# CON_MC_XMC_J11_64PIN.net
KiCad netlist of a schematic drawn in Altium Designer
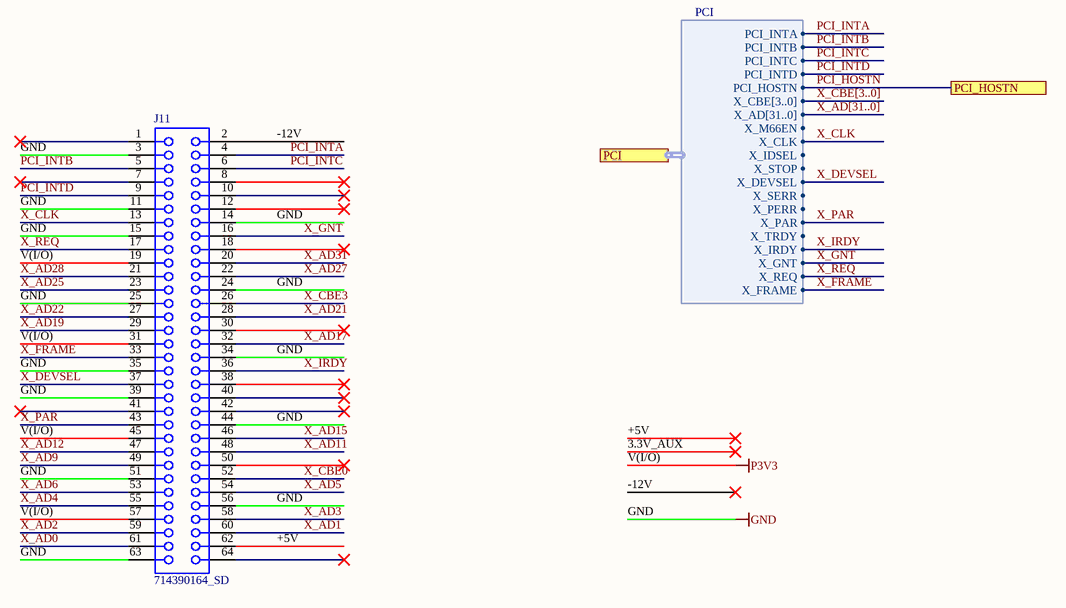
[diagram p0: CON_MC_XMC_J11_64PIN.SchDoc]

(export (version "E")
  (design (tool "Eeschema 10.0.6"))
  (components
    (comp (ref "J11")
      (value "714390164_SD")
      (footprint "BTB1-2V64F")
      (description "Board-to-Board Connector, Vertical, 2-Row, Pitch 1mm, 64-Position, Female")
      (fields (field (name "PUBLISHER") "Altium"))
      (libsource (lib "Altium Shanghai") (part "CMP-0001-00081-1"))
    )
  )
  (nets
    (net (code "15") (name "/+5V") (class "Default")
      (node (ref "J11") (pin "62") (pinfunction "62_62") (pintype "passive+no_connect"))
    )
    (net (code "16") (name "/-12V") (class "Default")
      (node (ref "J11") (pin "2") (pinfunction "2_2") (pintype "passive+no_connect"))
    )
    (net (code "19") (name "/PCI_INTA") (class "Default")
      (node (ref "J11") (pin "4") (pinfunction "4_4") (pintype "passive"))
    )
    (net (code "20") (name "/PCI_INTB") (class "Default")
      (node (ref "J11") (pin "5") (pinfunction "5_5") (pintype "passive"))
    )
    (net (code "21") (name "/PCI_INTC") (class "Default")
      (node (ref "J11") (pin "6") (pinfunction "6_6") (pintype "passive"))
    )
    (net (code "22") (name "/PCI_INTD") (class "Default")
      (node (ref "J11") (pin "9") (pinfunction "9_9") (pintype "passive"))
    )
    (net (code "24") (name "/X_AD0") (class "Default")
      (node (ref "J11") (pin "61") (pinfunction "61_61") (pintype "passive"))
    )
    (net (code "25") (name "/X_AD1") (class "Default")
      (node (ref "J11") (pin "60") (pinfunction "60_60") (pintype "passive"))
    )
    (net (code "26") (name "/X_AD2") (class "Default")
      (node (ref "J11") (pin "59") (pinfunction "59_59") (pintype "passive"))
    )
    (net (code "27") (name "/X_AD3") (class "Default")
      (node (ref "J11") (pin "58") (pinfunction "58_58") (pintype "passive"))
    )
    (net (code "28") (name "/X_AD4") (class "Default")
      (node (ref "J11") (pin "55") (pinfunction "55_55") (pintype "passive"))
    )
    (net (code "29") (name "/X_AD5") (class "Default")
      (node (ref "J11") (pin "54") (pinfunction "54_54") (pintype "passive"))
    )
    (net (code "30") (name "/X_AD6") (class "Default")
      (node (ref "J11") (pin "53") (pinfunction "53_53") (pintype "passive"))
    )
    (net (code "31") (name "/X_AD9") (class "Default")
      (node (ref "J11") (pin "49") (pinfunction "49_49") (pintype "passive"))
    )
    (net (code "32") (name "/X_AD11") (class "Default")
      (node (ref "J11") (pin "48") (pinfunction "48_48") (pintype "passive"))
    )
    (net (code "33") (name "/X_AD12") (class "Default")
      (node (ref "J11") (pin "47") (pinfunction "47_47") (pintype "passive"))
    )
    (net (code "34") (name "/X_AD15") (class "Default")
      (node (ref "J11") (pin "46") (pinfunction "46_46") (pintype "passive"))
    )
    (net (code "35") (name "/X_AD17") (class "Default")
      (node (ref "J11") (pin "32") (pinfunction "32_32") (pintype "passive"))
    )
    (net (code "36") (name "/X_AD19") (class "Default")
      (node (ref "J11") (pin "29") (pinfunction "29_29") (pintype "passive"))
    )
    (net (code "37") (name "/X_AD21") (class "Default")
      (node (ref "J11") (pin "28") (pinfunction "28_28") (pintype "passive"))
    )
    (net (code "38") (name "/X_AD22") (class "Default")
      (node (ref "J11") (pin "27") (pinfunction "27_27") (pintype "passive"))
    )
    (net (code "39") (name "/X_AD25") (class "Default")
      (node (ref "J11") (pin "23") (pinfunction "23_23") (pintype "passive"))
    )
    (net (code "40") (name "/X_AD27") (class "Default")
      (node (ref "J11") (pin "22") (pinfunction "22_22") (pintype "passive"))
    )
    (net (code "41") (name "/X_AD28") (class "Default")
      (node (ref "J11") (pin "21") (pinfunction "21_21") (pintype "passive"))
    )
    (net (code "42") (name "/X_AD31") (class "Default")
      (node (ref "J11") (pin "20") (pinfunction "20_20") (pintype "passive"))
    )
    (net (code "44") (name "/X_CBE0") (class "Default")
      (node (ref "J11") (pin "52") (pinfunction "52_52") (pintype "passive"))
    )
    (net (code "45") (name "/X_CBE3") (class "Default")
      (node (ref "J11") (pin "26") (pinfunction "26_26") (pintype "passive"))
    )
    (net (code "46") (name "/X_CLK") (class "Default")
      (node (ref "J11") (pin "13") (pinfunction "13_13") (pintype "passive"))
    )
    (net (code "47") (name "/X_DEVSEL") (class "Default")
      (node (ref "J11") (pin "37") (pinfunction "37_37") (pintype "passive"))
    )
    (net (code "48") (name "/X_FRAME") (class "Default")
      (node (ref "J11") (pin "33") (pinfunction "33_33") (pintype "passive"))
    )
    (net (code "49") (name "/X_GNT") (class "Default")
      (node (ref "J11") (pin "16") (pinfunction "16_16") (pintype "passive"))
    )
    (net (code "50") (name "/X_IRDY") (class "Default")
      (node (ref "J11") (pin "36") (pinfunction "36_36") (pintype "passive"))
    )
    (net (code "51") (name "/X_PAR") (class "Default")
      (node (ref "J11") (pin "43") (pinfunction "43_43") (pintype "passive"))
    )
    (net (code "52") (name "/X_REQ") (class "Default")
      (node (ref "J11") (pin "17") (pinfunction "17_17") (pintype "passive"))
    )
    (net (code "54") (name "GND") (class "Default")
      (node (ref "J11") (pin "11") (pinfunction "11_11") (pintype "passive"))
      (node (ref "J11") (pin "14") (pinfunction "14_14") (pintype "passive"))
      (node (ref "J11") (pin "15") (pinfunction "15_15") (pintype "passive"))
      (node (ref "J11") (pin "24") (pinfunction "24_24") (pintype "passive"))
      (node (ref "J11") (pin "25") (pinfunction "25_25") (pintype "passive"))
      (node (ref "J11") (pin "3") (pinfunction "3_3") (pintype "passive"))
      (node (ref "J11") (pin "34") (pinfunction "34_34") (pintype "passive"))
      (node (ref "J11") (pin "35") (pinfunction "35_35") (pintype "passive"))
      (node (ref "J11") (pin "39") (pinfunction "39_39") (pintype "passive"))
      (node (ref "J11") (pin "44") (pinfunction "44_44") (pintype "passive"))
      (node (ref "J11") (pin "51") (pinfunction "51_51") (pintype "passive"))
      (node (ref "J11") (pin "56") (pinfunction "56_56") (pintype "passive"))
      (node (ref "J11") (pin "63") (pinfunction "63_63") (pintype "passive"))
    )
    (net (code "55") (name "P3V3") (class "Default")
      (node (ref "J11") (pin "19") (pinfunction "19_19") (pintype "passive"))
      (node (ref "J11") (pin "31") (pinfunction "31_31") (pintype "passive"))
      (node (ref "J11") (pin "45") (pinfunction "45_45") (pintype "passive"))
      (node (ref "J11") (pin "57") (pinfunction "57_57") (pintype "passive"))
    )
    (net (code "56") (name "unconnected-(J11-Pad1)") (class "Default")
      (node (ref "J11") (pin "1") (pinfunction "1_1") (pintype "passive+no_connect"))
    )
    (net (code "57") (name "unconnected-(J11-Pad7)") (class "Default")
      (node (ref "J11") (pin "7") (pinfunction "7_7") (pintype "passive+no_connect"))
    )
    (net (code "58") (name "unconnected-(J11-Pad8)") (class "Default")
      (node (ref "J11") (pin "8") (pinfunction "8_8") (pintype "passive+no_connect"))
    )
    (net (code "59") (name "unconnected-(J11-Pad10)") (class "Default")
      (node (ref "J11") (pin "10") (pinfunction "10_10") (pintype "passive+no_connect"))
    )
    (net (code "60") (name "unconnected-(J11-Pad12)") (class "Default")
      (node (ref "J11") (pin "12") (pinfunction "12_12") (pintype "passive+no_connect"))
    )
    (net (code "61") (name "unconnected-(J11-Pad18)") (class "Default")
      (node (ref "J11") (pin "18") (pinfunction "18_18") (pintype "passive+no_connect"))
    )
    (net (code "62") (name "unconnected-(J11-Pad30)") (class "Default")
      (node (ref "J11") (pin "30") (pinfunction "30_30") (pintype "passive+no_connect"))
    )
    (net (code "63") (name "unconnected-(J11-Pad38)") (class "Default")
      (node (ref "J11") (pin "38") (pinfunction "38_38") (pintype "passive+no_connect"))
    )
    (net (code "64") (name "unconnected-(J11-Pad40)") (class "Default")
      (node (ref "J11") (pin "40") (pinfunction "40_40") (pintype "passive+no_connect"))
    )
    (net (code "65") (name "unconnected-(J11-Pad41)") (class "Default")
      (node (ref "J11") (pin "41") (pinfunction "41_41") (pintype "passive+no_connect"))
    )
    (net (code "66") (name "unconnected-(J11-Pad42)") (class "Default")
      (node (ref "J11") (pin "42") (pinfunction "42_42") (pintype "passive+no_connect"))
    )
    (net (code "67") (name "unconnected-(J11-Pad50)") (class "Default")
      (node (ref "J11") (pin "50") (pinfunction "50_50") (pintype "passive+no_connect"))
    )
    (net (code "68") (name "unconnected-(J11-Pad64)") (class "Default")
      (node (ref "J11") (pin "64") (pinfunction "64_64") (pintype "passive+no_connect"))
    )
  )
)
